# Support.net
KiCad netlist of a schematic drawn in Altium Designer
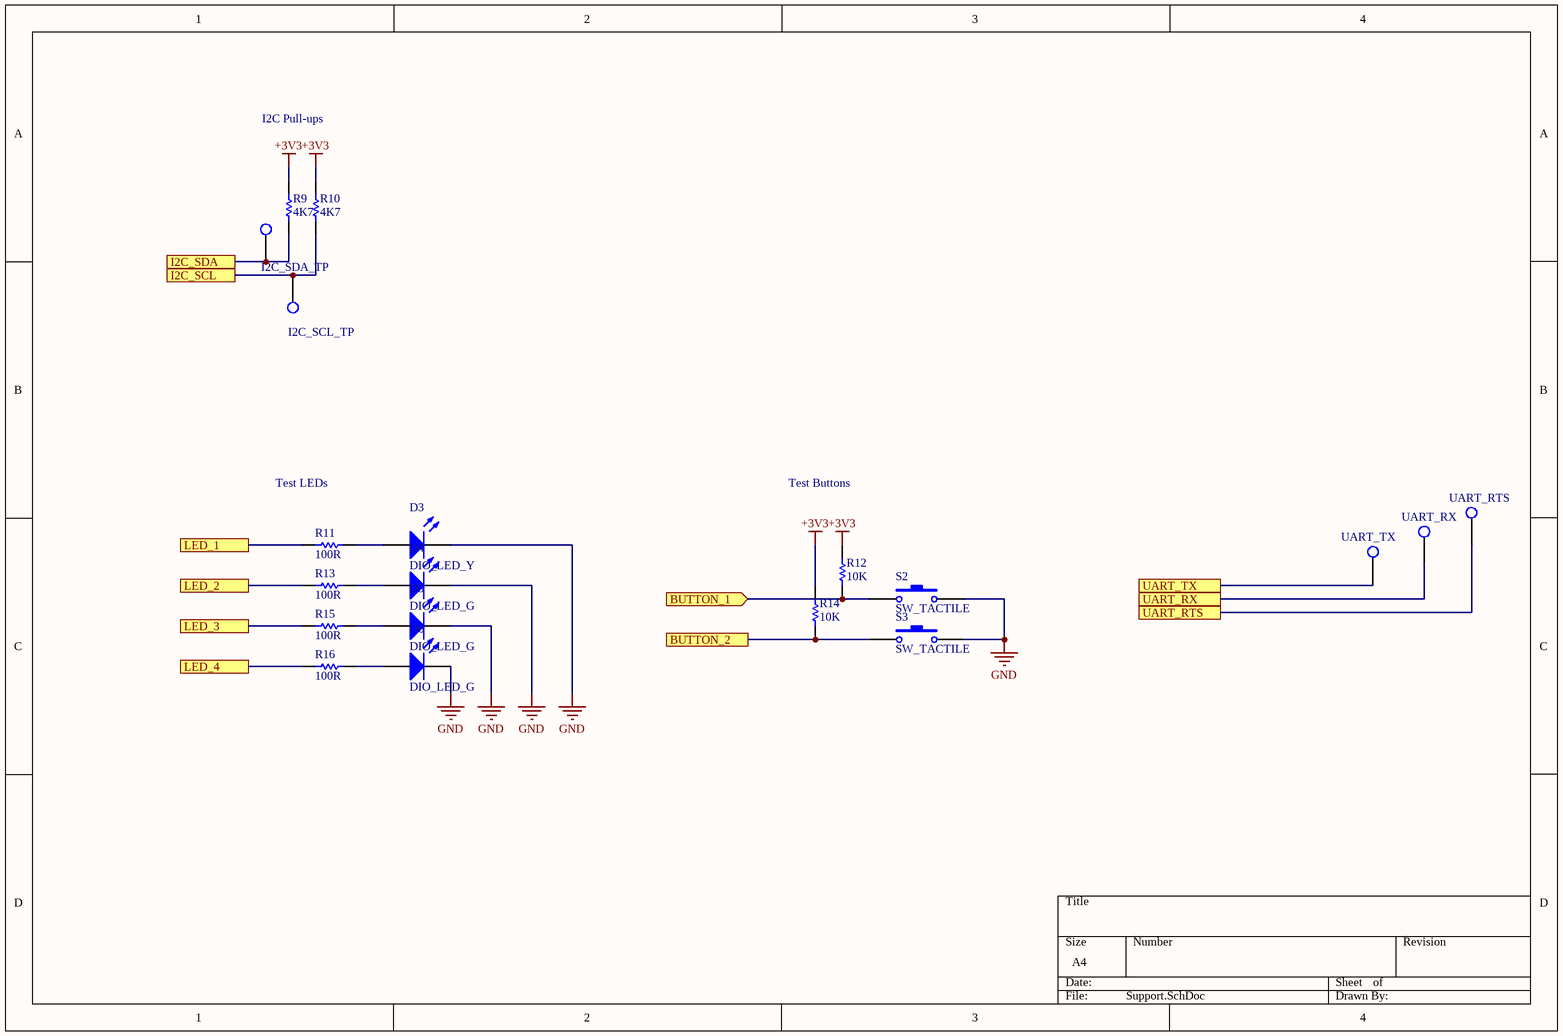
[diagram p0: Support.SchDoc]

(export (version "E")
  (design (tool "Eeschema 10.0.6"))
  (components
    (comp (ref "D3")
      (value "DIO_LED_Y")
      (footprint "LED_0805")
      (description "LED YELLOW DIFFUSED 0805 SMD")
      (fields (field (name "PART NUMBER") "LY R976-PS-36") (field (name "MANUFACTURER") "OSRAM"))
      (libsource (lib "UWRT_Schematic_Library_2019") (part "DIO_LED_Y"))
    )
    (comp (ref "D4")
      (value "DIO_LED_G")
      (footprint "LED_0805")
      (description "LED GREEN DIFFUSED 0805 SMD")
      (fields (field (name "PART NUMBER") "LG R971-KN-1") (field (name "MANUFACTURER") "OSRAM"))
      (libsource (lib "UWRT_Schematic_Library_2019") (part "DIO_LED_G"))
    )
    (comp (ref "D5")
      (value "DIO_LED_G")
      (footprint "LED_0805")
      (description "LED GREEN DIFFUSED 0805 SMD")
      (fields (field (name "PART NUMBER") "LG R971-KN-1") (field (name "MANUFACTURER") "OSRAM"))
      (libsource (lib "UWRT_Schematic_Library_2019") (part "DIO_LED_G"))
    )
    (comp (ref "D6")
      (value "DIO_LED_G")
      (footprint "LED_0805")
      (description "LED GREEN DIFFUSED 0805 SMD")
      (fields (field (name "PART NUMBER") "LG R971-KN-1") (field (name "MANUFACTURER") "OSRAM"))
      (libsource (lib "UWRT_Schematic_Library_2019") (part "DIO_LED_G"))
    )
    (comp (ref "R9")
      (value "4K7")
      (footprint "RESC0603(1608)_N")
      (description "RES SMD 4.7K OHM 5% 1/10W 0603")
      (fields (field (name "MANUFACTURER") "Yageo") (field (name "TOLERANCE") "5%"))
      (libsource (lib "UWRT_Schematic_Library_2019") (part "RES_4K7_0603"))
    )
    (comp (ref "R10")
      (value "4K7")
      (footprint "RESC0603(1608)_N")
      (description "RES SMD 4.7K OHM 5% 1/10W 0603")
      (fields (field (name "MANUFACTURER") "Yageo") (field (name "TOLERANCE") "5%"))
      (libsource (lib "UWRT_Schematic_Library_2019") (part "RES_4K7_0603"))
    )
    (comp (ref "R11")
      (value "100R")
      (footprint "RESC0603(1608)_N")
      (description "RES SMD 100 OHM 1% 1/10W 0603")
      (fields (field (name "MANUFACTURER") "Yageo") (field (name "TOLERANCE") "1%"))
      (libsource (lib "UWRT_Schematic_Library_2019") (part "RES_100R_0603"))
    )
    (comp (ref "R12")
      (value "10K")
      (footprint "RESC0603(1608)_N")
      (description "RES SMD 10K OHM 5% 1/10W 0603")
      (fields (field (name "MANUFACTURER") "Yageo") (field (name "TOLERANCE") "5%"))
      (libsource (lib "UWRT_Schematic_Library_2019") (part "RES_10K_0603"))
    )
    (comp (ref "R13")
      (value "100R")
      (footprint "RESC0603(1608)_N")
      (description "RES SMD 100 OHM 1% 1/10W 0603")
      (fields (field (name "MANUFACTURER") "Yageo") (field (name "TOLERANCE") "1%"))
      (libsource (lib "UWRT_Schematic_Library_2019") (part "RES_100R_0603"))
    )
    (comp (ref "R14")
      (value "10K")
      (footprint "RESC0603(1608)_N")
      (description "RES SMD 10K OHM 5% 1/10W 0603")
      (fields (field (name "MANUFACTURER") "Yageo") (field (name "TOLERANCE") "5%"))
      (libsource (lib "UWRT_Schematic_Library_2019") (part "RES_10K_0603"))
    )
    (comp (ref "R15")
      (value "100R")
      (footprint "RESC0603(1608)_N")
      (description "RES SMD 100 OHM 1% 1/10W 0603")
      (fields (field (name "MANUFACTURER") "Yageo") (field (name "TOLERANCE") "1%"))
      (libsource (lib "UWRT_Schematic_Library_2019") (part "RES_100R_0603"))
    )
    (comp (ref "R16")
      (value "100R")
      (footprint "RESC0603(1608)_N")
      (description "RES SMD 100 OHM 1% 1/10W 0603")
      (fields (field (name "MANUFACTURER") "Yageo") (field (name "TOLERANCE") "1%"))
      (libsource (lib "UWRT_Schematic_Library_2019") (part "RES_100R_0603"))
    )
    (comp (ref "S2")
      (value "SW_TACTILE")
      (footprint "B3U-1100P")
      (description "Tactile Switch (Grey)")
      (fields
        (field (name "MANUFACTURER PART NUMBER") "B3U-1100P")
        (field (name "DIGIKEY PART NUMBER") "SW1021TR-ND")
      )
      (libsource (lib "UWRT_Schematic_Library_2019") (part "SW_TACTILE"))
    )
    (comp (ref "S3")
      (value "SW_TACTILE")
      (footprint "B3U-1100P")
      (description "Tactile Switch (Grey)")
      (fields
        (field (name "MANUFACTURER PART NUMBER") "B3U-1100P")
        (field (name "DIGIKEY PART NUMBER") "SW1021TR-ND")
      )
      (libsource (lib "UWRT_Schematic_Library_2019") (part "SW_TACTILE"))
    )
    (comp (ref "TP7")
      (value "I2C_SDA_TP")
      (footprint "TESTPOINT_LOOP")
      (libsource (lib "UWRT_Schematic_Library_2019") (part "TESTPOINT_LOOP"))
    )
    (comp (ref "TP8")
      (value "I2C_SCL_TP")
      (footprint "TESTPOINT_LOOP")
      (libsource (lib "UWRT_Schematic_Library_2019") (part "TESTPOINT_LOOP"))
    )
    (comp (ref "TP9")
      (value "UART_RTS")
      (footprint "TESTPOINT_LOOP")
      (libsource (lib "UWRT_Schematic_Library_2019") (part "TESTPOINT_LOOP"))
    )
    (comp (ref "TP10")
      (value "UART_RX")
      (footprint "TESTPOINT_LOOP")
      (libsource (lib "UWRT_Schematic_Library_2019") (part "TESTPOINT_LOOP"))
    )
    (comp (ref "TP11")
      (value "UART_TX")
      (footprint "TESTPOINT_LOOP")
      (libsource (lib "UWRT_Schematic_Library_2019") (part "TESTPOINT_LOOP"))
    )
  )
  (nets
    (net (code "1") (name "+3V3") (class "Default")
      (node (ref "R10") (pin "2") (pinfunction "2_2") (pintype "passive"))
      (node (ref "R12") (pin "2") (pinfunction "2_2") (pintype "passive"))
      (node (ref "R14") (pin "1") (pinfunction "1_1") (pintype "passive"))
      (node (ref "R9") (pin "2") (pinfunction "2_2") (pintype "passive"))
    )
    (net (code "2") (name "/BUTTON_1") (class "Default")
      (node (ref "R12") (pin "1") (pinfunction "1_1") (pintype "passive"))
      (node (ref "S2") (pin "1") (pinfunction "1_1") (pintype "passive"))
    )
    (net (code "3") (name "/BUTTON_2") (class "Default")
      (node (ref "R14") (pin "2") (pinfunction "2_2") (pintype "passive"))
      (node (ref "S3") (pin "1") (pinfunction "1_1") (pintype "passive"))
    )
    (net (code "4") (name "/I2C_SCL") (class "Default")
      (node (ref "R10") (pin "1") (pinfunction "1_1") (pintype "passive"))
      (node (ref "TP8") (pin "1") (pinfunction "=value_1") (pintype "passive"))
    )
    (net (code "5") (name "/I2C_SDA") (class "Default")
      (node (ref "R9") (pin "1") (pinfunction "1_1") (pintype "passive"))
      (node (ref "TP7") (pin "1") (pinfunction "=value_1") (pintype "passive"))
    )
    (net (code "6") (name "/LED_1") (class "Default")
      (node (ref "R11") (pin "1") (pinfunction "1_1") (pintype "passive"))
    )
    (net (code "7") (name "/LED_2") (class "Default")
      (node (ref "R13") (pin "1") (pinfunction "1_1") (pintype "passive"))
    )
    (net (code "8") (name "/LED_3") (class "Default")
      (node (ref "R15") (pin "1") (pinfunction "1_1") (pintype "passive"))
    )
    (net (code "9") (name "/LED_4") (class "Default")
      (node (ref "R16") (pin "1") (pinfunction "1_1") (pintype "passive"))
    )
    (net (code "10") (name "/UART_RTS") (class "Default")
      (node (ref "TP9") (pin "1") (pinfunction "=value_1") (pintype "passive"))
    )
    (net (code "11") (name "/UART_RX") (class "Default")
      (node (ref "TP10") (pin "1") (pinfunction "=value_1") (pintype "passive"))
    )
    (net (code "12") (name "/UART_TX") (class "Default")
      (node (ref "TP11") (pin "1") (pinfunction "=value_1") (pintype "passive"))
    )
    (net (code "13") (name "GND") (class "Default")
      (node (ref "D3") (pin "2") (pinfunction "K_2") (pintype "passive"))
      (node (ref "D4") (pin "2") (pinfunction "K_2") (pintype "passive"))
      (node (ref "D5") (pin "2") (pinfunction "K_2") (pintype "passive"))
      (node (ref "D6") (pin "2") (pinfunction "K_2") (pintype "passive"))
      (node (ref "S2") (pin "2") (pinfunction "2_2") (pintype "passive"))
      (node (ref "S3") (pin "2") (pinfunction "2_2") (pintype "passive"))
    )
    (net (code "14") (name "Net-(D3-A)") (class "Default")
      (node (ref "D3") (pin "1") (pinfunction "A_1") (pintype "passive"))
      (node (ref "R11") (pin "2") (pinfunction "2_2") (pintype "passive"))
    )
    (net (code "15") (name "Net-(D4-A)") (class "Default")
      (node (ref "D4") (pin "1") (pinfunction "A_1") (pintype "passive"))
      (node (ref "R13") (pin "2") (pinfunction "2_2") (pintype "passive"))
    )
    (net (code "16") (name "Net-(D5-A)") (class "Default")
      (node (ref "D5") (pin "1") (pinfunction "A_1") (pintype "passive"))
      (node (ref "R15") (pin "2") (pinfunction "2_2") (pintype "passive"))
    )
    (net (code "17") (name "Net-(D6-A)") (class "Default")
      (node (ref "D6") (pin "1") (pinfunction "A_1") (pintype "passive"))
      (node (ref "R16") (pin "2") (pinfunction "2_2") (pintype "passive"))
    )
  )
)
